# B2B_Connector.net
KiCad netlist of a schematic drawn in Altium Designer
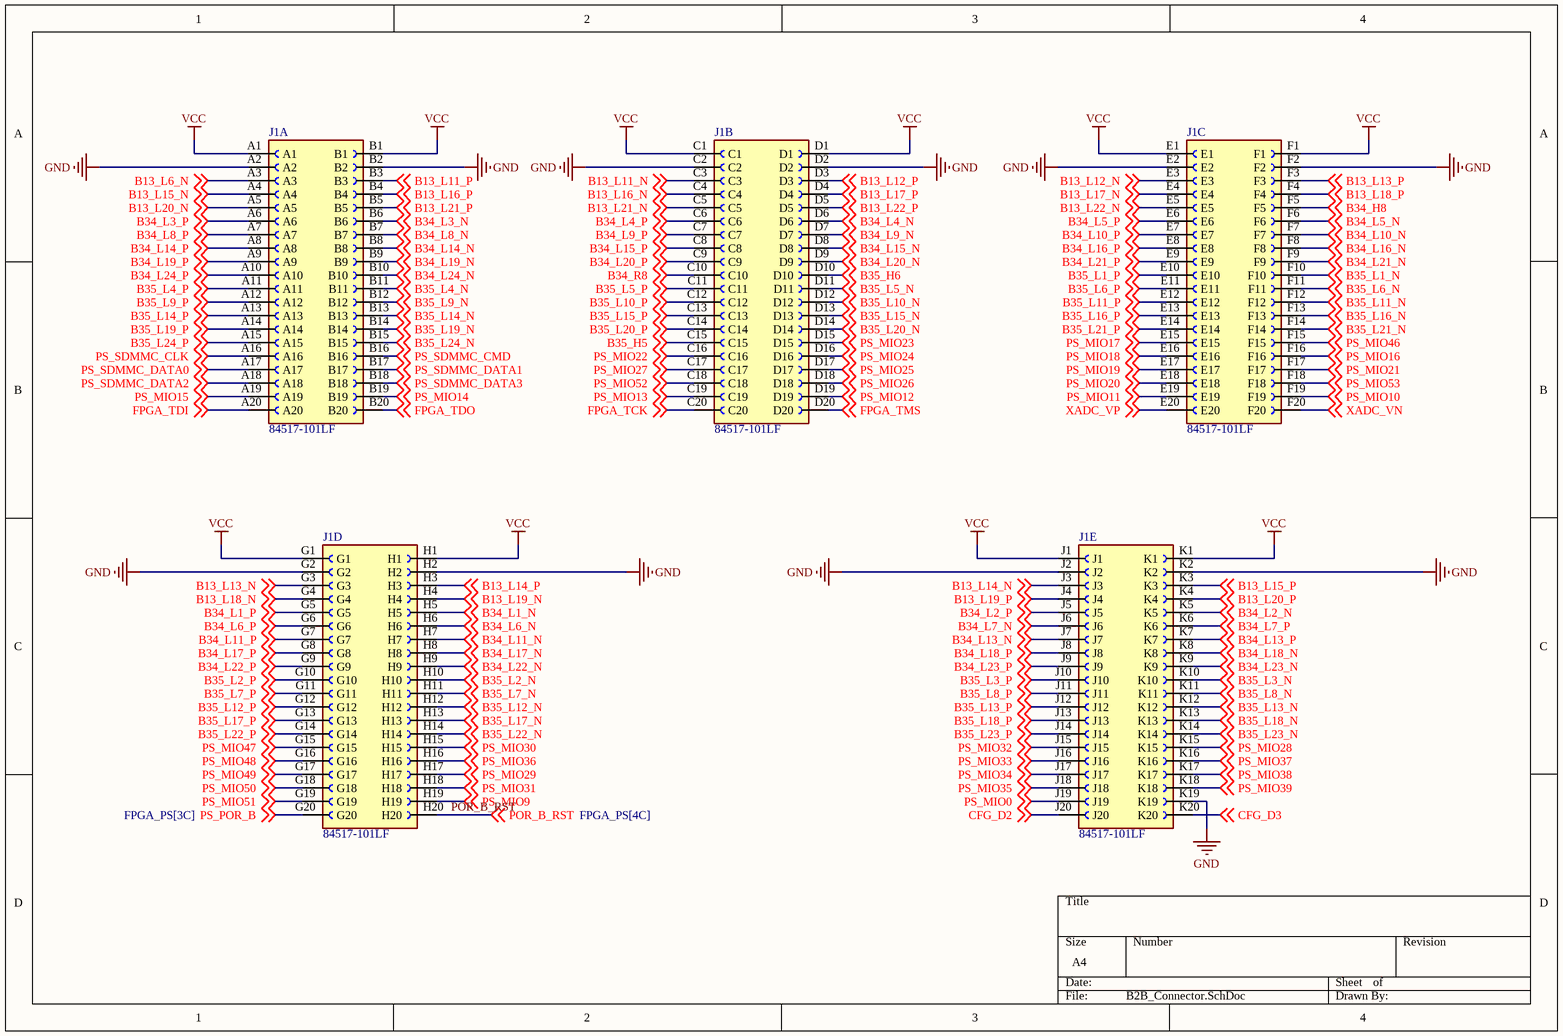
[diagram p0: B2B_Connector.SchDoc]

(export (version "E")
  (design (tool "Eeschema 10.0.6"))
  (components
    (comp (ref "J1")
      (value "84517-101LF")
      (footprint "AMPHENOL_84517-101LF")
      (description "MEG-ARRAY LEAD FREE-200 POS RECP 4MM W/CAP ¦ Amphenol FCI (Amphenol CS) 84517-101LF")
      (fields (field (name "MF") "Amphenol ICC (FCI)"))
      (libsource (lib "84517-101LF") (part "84517-101LF"))
    )
  )
  (nets
    (net (code "1") (name "B13_L6_N") (class "Default")
      (node (ref "J1") (pin "A3") (pinfunction "A3_A3") (pintype "passive"))
    )
    (net (code "2") (name "B13_L11_N") (class "Default")
      (node (ref "J1") (pin "C3") (pinfunction "C3_C3") (pintype "passive"))
    )
    (net (code "3") (name "B13_L11_P") (class "Default")
      (node (ref "J1") (pin "B3") (pinfunction "B3_B3") (pintype "passive"))
    )
    (net (code "4") (name "B13_L12_N") (class "Default")
      (node (ref "J1") (pin "E3") (pinfunction "E3_E3") (pintype "passive"))
    )
    (net (code "5") (name "B13_L12_P") (class "Default")
      (node (ref "J1") (pin "D3") (pinfunction "D3_D3") (pintype "passive"))
    )
    (net (code "6") (name "B13_L13_N") (class "Default")
      (node (ref "J1") (pin "G3") (pinfunction "G3_G3") (pintype "passive"))
    )
    (net (code "7") (name "B13_L13_P") (class "Default")
      (node (ref "J1") (pin "F3") (pinfunction "F3_F3") (pintype "passive"))
    )
    (net (code "8") (name "B13_L14_N") (class "Default")
      (node (ref "J1") (pin "J3") (pinfunction "J3_J3") (pintype "passive"))
    )
    (net (code "9") (name "B13_L14_P") (class "Default")
      (node (ref "J1") (pin "H3") (pinfunction "H3_H3") (pintype "passive"))
    )
    (net (code "10") (name "B13_L15_N") (class "Default")
      (node (ref "J1") (pin "A4") (pinfunction "A4_A4") (pintype "passive"))
    )
    (net (code "11") (name "B13_L15_P") (class "Default")
      (node (ref "J1") (pin "K3") (pinfunction "K3_K3") (pintype "passive"))
    )
    (net (code "12") (name "B13_L16_N") (class "Default")
      (node (ref "J1") (pin "C4") (pinfunction "C4_C4") (pintype "passive"))
    )
    (net (code "13") (name "B13_L16_P") (class "Default")
      (node (ref "J1") (pin "B4") (pinfunction "B4_B4") (pintype "passive"))
    )
    (net (code "14") (name "B13_L17_N") (class "Default")
      (node (ref "J1") (pin "E4") (pinfunction "E4_E4") (pintype "passive"))
    )
    (net (code "15") (name "B13_L17_P") (class "Default")
      (node (ref "J1") (pin "D4") (pinfunction "D4_D4") (pintype "passive"))
    )
    (net (code "16") (name "B13_L18_N") (class "Default")
      (node (ref "J1") (pin "G4") (pinfunction "G4_G4") (pintype "passive"))
    )
    (net (code "17") (name "B13_L18_P") (class "Default")
      (node (ref "J1") (pin "F4") (pinfunction "F4_F4") (pintype "passive"))
    )
    (net (code "18") (name "B13_L19_N") (class "Default")
      (node (ref "J1") (pin "H4") (pinfunction "H4_H4") (pintype "passive"))
    )
    (net (code "19") (name "B13_L19_P") (class "Default")
      (node (ref "J1") (pin "J4") (pinfunction "J4_J4") (pintype "passive"))
    )
    (net (code "20") (name "B13_L20_N") (class "Default")
      (node (ref "J1") (pin "A5") (pinfunction "A5_A5") (pintype "passive"))
    )
    (net (code "21") (name "B13_L20_P") (class "Default")
      (node (ref "J1") (pin "K4") (pinfunction "K4_K4") (pintype "passive"))
    )
    (net (code "22") (name "B13_L21_N") (class "Default")
      (node (ref "J1") (pin "C5") (pinfunction "C5_C5") (pintype "passive"))
    )
    (net (code "23") (name "B13_L21_P") (class "Default")
      (node (ref "J1") (pin "B5") (pinfunction "B5_B5") (pintype "passive"))
    )
    (net (code "24") (name "B13_L22_N") (class "Default")
      (node (ref "J1") (pin "E5") (pinfunction "E5_E5") (pintype "passive"))
    )
    (net (code "25") (name "B13_L22_P") (class "Default")
      (node (ref "J1") (pin "D5") (pinfunction "D5_D5") (pintype "passive"))
    )
    (net (code "26") (name "B34_H8") (class "Default")
      (node (ref "J1") (pin "F5") (pinfunction "F5_F5") (pintype "passive"))
    )
    (net (code "27") (name "B34_L1_N") (class "Default")
      (node (ref "J1") (pin "H5") (pinfunction "H5_H5") (pintype "passive"))
    )
    (net (code "28") (name "B34_L1_P") (class "Default")
      (node (ref "J1") (pin "G5") (pinfunction "G5_G5") (pintype "passive"))
    )
    (net (code "29") (name "B34_L2_N") (class "Default")
      (node (ref "J1") (pin "K5") (pinfunction "K5_K5") (pintype "passive"))
    )
    (net (code "30") (name "B34_L2_P") (class "Default")
      (node (ref "J1") (pin "J5") (pinfunction "J5_J5") (pintype "passive"))
    )
    (net (code "31") (name "B34_L3_N") (class "Default")
      (node (ref "J1") (pin "B6") (pinfunction "B6_B6") (pintype "passive"))
    )
    (net (code "32") (name "B34_L3_P") (class "Default")
      (node (ref "J1") (pin "A6") (pinfunction "A6_A6") (pintype "passive"))
    )
    (net (code "33") (name "B34_L4_N") (class "Default")
      (node (ref "J1") (pin "D6") (pinfunction "D6_D6") (pintype "passive"))
    )
    (net (code "34") (name "B34_L4_P") (class "Default")
      (node (ref "J1") (pin "C6") (pinfunction "C6_C6") (pintype "passive"))
    )
    (net (code "35") (name "B34_L5_N") (class "Default")
      (node (ref "J1") (pin "F6") (pinfunction "F6_F6") (pintype "passive"))
    )
    (net (code "36") (name "B34_L5_P") (class "Default")
      (node (ref "J1") (pin "E6") (pinfunction "E6_E6") (pintype "passive"))
    )
    (net (code "37") (name "B34_L6_N") (class "Default")
      (node (ref "J1") (pin "H6") (pinfunction "H6_H6") (pintype "passive"))
    )
    (net (code "38") (name "B34_L6_P") (class "Default")
      (node (ref "J1") (pin "G6") (pinfunction "G6_G6") (pintype "passive"))
    )
    (net (code "39") (name "B34_L7_N") (class "Default")
      (node (ref "J1") (pin "J6") (pinfunction "J6_J6") (pintype "passive"))
    )
    (net (code "40") (name "B34_L7_P") (class "Default")
      (node (ref "J1") (pin "K6") (pinfunction "K6_K6") (pintype "passive"))
    )
    (net (code "41") (name "B34_L8_N") (class "Default")
      (node (ref "J1") (pin "B7") (pinfunction "B7_B7") (pintype "passive"))
    )
    (net (code "42") (name "B34_L8_P") (class "Default")
      (node (ref "J1") (pin "A7") (pinfunction "A7_A7") (pintype "passive"))
    )
    (net (code "43") (name "B34_L9_N") (class "Default")
      (node (ref "J1") (pin "D7") (pinfunction "D7_D7") (pintype "passive"))
    )
    (net (code "44") (name "B34_L9_P") (class "Default")
      (node (ref "J1") (pin "C7") (pinfunction "C7_C7") (pintype "passive"))
    )
    (net (code "45") (name "B34_L10_N") (class "Default")
      (node (ref "J1") (pin "F7") (pinfunction "F7_F7") (pintype "passive"))
    )
    (net (code "46") (name "B34_L10_P") (class "Default")
      (node (ref "J1") (pin "E7") (pinfunction "E7_E7") (pintype "passive"))
    )
    (net (code "47") (name "B34_L11_N") (class "Default")
      (node (ref "J1") (pin "H7") (pinfunction "H7_H7") (pintype "passive"))
    )
    (net (code "48") (name "B34_L11_P") (class "Default")
      (node (ref "J1") (pin "G7") (pinfunction "G7_G7") (pintype "passive"))
    )
    (net (code "49") (name "B34_L13_N") (class "Default")
      (node (ref "J1") (pin "J7") (pinfunction "J7_J7") (pintype "passive"))
    )
    (net (code "50") (name "B34_L13_P") (class "Default")
      (node (ref "J1") (pin "K7") (pinfunction "K7_K7") (pintype "passive"))
    )
    (net (code "51") (name "B34_L14_N") (class "Default")
      (node (ref "J1") (pin "B8") (pinfunction "B8_B8") (pintype "passive"))
    )
    (net (code "52") (name "B34_L14_P") (class "Default")
      (node (ref "J1") (pin "A8") (pinfunction "A8_A8") (pintype "passive"))
    )
    (net (code "53") (name "B34_L15_N") (class "Default")
      (node (ref "J1") (pin "D8") (pinfunction "D8_D8") (pintype "passive"))
    )
    (net (code "54") (name "B34_L15_P") (class "Default")
      (node (ref "J1") (pin "C8") (pinfunction "C8_C8") (pintype "passive"))
    )
    (net (code "55") (name "B34_L16_N") (class "Default")
      (node (ref "J1") (pin "F8") (pinfunction "F8_F8") (pintype "passive"))
    )
    (net (code "56") (name "B34_L16_P") (class "Default")
      (node (ref "J1") (pin "E8") (pinfunction "E8_E8") (pintype "passive"))
    )
    (net (code "57") (name "B34_L17_N") (class "Default")
      (node (ref "J1") (pin "H8") (pinfunction "H8_H8") (pintype "passive"))
    )
    (net (code "58") (name "B34_L17_P") (class "Default")
      (node (ref "J1") (pin "G8") (pinfunction "G8_G8") (pintype "passive"))
    )
    (net (code "59") (name "B34_L18_N") (class "Default")
      (node (ref "J1") (pin "K8") (pinfunction "K8_K8") (pintype "passive"))
    )
    (net (code "60") (name "B34_L18_P") (class "Default")
      (node (ref "J1") (pin "J8") (pinfunction "J8_J8") (pintype "passive"))
    )
    (net (code "61") (name "B34_L19_N") (class "Default")
      (node (ref "J1") (pin "B9") (pinfunction "B9_B9") (pintype "passive"))
    )
    (net (code "62") (name "B34_L19_P") (class "Default")
      (node (ref "J1") (pin "A9") (pinfunction "A9_A9") (pintype "passive"))
    )
    (net (code "63") (name "B34_L20_N") (class "Default")
      (node (ref "J1") (pin "D9") (pinfunction "D9_D9") (pintype "passive"))
    )
    (net (code "64") (name "B34_L20_P") (class "Default")
      (node (ref "J1") (pin "C9") (pinfunction "C9_C9") (pintype "passive"))
    )
    (net (code "65") (name "B34_L21_N") (class "Default")
      (node (ref "J1") (pin "F9") (pinfunction "F9_F9") (pintype "passive"))
    )
    (net (code "66") (name "B34_L21_P") (class "Default")
      (node (ref "J1") (pin "E9") (pinfunction "E9_E9") (pintype "passive"))
    )
    (net (code "67") (name "B34_L22_N") (class "Default")
      (node (ref "J1") (pin "H9") (pinfunction "H9_H9") (pintype "passive"))
    )
    (net (code "68") (name "B34_L22_P") (class "Default")
      (node (ref "J1") (pin "G9") (pinfunction "G9_G9") (pintype "passive"))
    )
    (net (code "69") (name "B34_L23_N") (class "Default")
      (node (ref "J1") (pin "K9") (pinfunction "K9_K9") (pintype "passive"))
    )
    (net (code "70") (name "B34_L23_P") (class "Default")
      (node (ref "J1") (pin "J9") (pinfunction "J9_J9") (pintype "passive"))
    )
    (net (code "71") (name "B34_L24_N") (class "Default")
      (node (ref "J1") (pin "B10") (pinfunction "B10_B10") (pintype "passive"))
    )
    (net (code "72") (name "B34_L24_P") (class "Default")
      (node (ref "J1") (pin "A10") (pinfunction "A10_A10") (pintype "passive"))
    )
    (net (code "73") (name "B34_R8") (class "Default")
      (node (ref "J1") (pin "C10") (pinfunction "C10_C10") (pintype "passive"))
    )
    (net (code "74") (name "B35_H5") (class "Default")
      (node (ref "J1") (pin "C15") (pinfunction "C15_C15") (pintype "passive"))
    )
    (net (code "75") (name "B35_H6") (class "Default")
      (node (ref "J1") (pin "D10") (pinfunction "D10_D10") (pintype "passive"))
    )
    (net (code "76") (name "B35_L1_N") (class "Default")
      (node (ref "J1") (pin "F10") (pinfunction "F10_F10") (pintype "passive"))
    )
    (net (code "77") (name "B35_L1_P") (class "Default")
      (node (ref "J1") (pin "E10") (pinfunction "E10_E10") (pintype "passive"))
    )
    (net (code "78") (name "B35_L2_N") (class "Default")
      (node (ref "J1") (pin "H10") (pinfunction "H10_H10") (pintype "passive"))
    )
    (net (code "79") (name "B35_L2_P") (class "Default")
      (node (ref "J1") (pin "G10") (pinfunction "G10_G10") (pintype "passive"))
    )
    (net (code "80") (name "B35_L3_N") (class "Default")
      (node (ref "J1") (pin "K10") (pinfunction "K10_K10") (pintype "passive"))
    )
    (net (code "81") (name "B35_L3_P") (class "Default")
      (node (ref "J1") (pin "J10") (pinfunction "J10_J10") (pintype "passive"))
    )
    (net (code "82") (name "B35_L4_N") (class "Default")
      (node (ref "J1") (pin "B11") (pinfunction "B11_B11") (pintype "passive"))
    )
    (net (code "83") (name "B35_L4_P") (class "Default")
      (node (ref "J1") (pin "A11") (pinfunction "A11_A11") (pintype "passive"))
    )
    (net (code "84") (name "B35_L5_N") (class "Default")
      (node (ref "J1") (pin "D11") (pinfunction "D11_D11") (pintype "passive"))
    )
    (net (code "85") (name "B35_L5_P") (class "Default")
      (node (ref "J1") (pin "C11") (pinfunction "C11_C11") (pintype "passive"))
    )
    (net (code "86") (name "B35_L6_N") (class "Default")
      (node (ref "J1") (pin "F11") (pinfunction "F11_F11") (pintype "passive"))
    )
    (net (code "87") (name "B35_L6_P") (class "Default")
      (node (ref "J1") (pin "E11") (pinfunction "E11_E11") (pintype "passive"))
    )
    (net (code "88") (name "B35_L7_N") (class "Default")
      (node (ref "J1") (pin "H11") (pinfunction "H11_H11") (pintype "passive"))
    )
    (net (code "89") (name "B35_L7_P") (class "Default")
      (node (ref "J1") (pin "G11") (pinfunction "G11_G11") (pintype "passive"))
    )
    (net (code "90") (name "B35_L8_N") (class "Default")
      (node (ref "J1") (pin "K11") (pinfunction "K11_K11") (pintype "passive"))
    )
    (net (code "91") (name "B35_L8_P") (class "Default")
      (node (ref "J1") (pin "J11") (pinfunction "J11_J11") (pintype "passive"))
    )
    (net (code "92") (name "B35_L9_N") (class "Default")
      (node (ref "J1") (pin "B12") (pinfunction "B12_B12") (pintype "passive"))
    )
    (net (code "93") (name "B35_L9_P") (class "Default")
      (node (ref "J1") (pin "A12") (pinfunction "A12_A12") (pintype "passive"))
    )
    (net (code "94") (name "B35_L10_N") (class "Default")
      (node (ref "J1") (pin "D12") (pinfunction "D12_D12") (pintype "passive"))
    )
    (net (code "95") (name "B35_L10_P") (class "Default")
      (node (ref "J1") (pin "C12") (pinfunction "C12_C12") (pintype "passive"))
    )
    (net (code "96") (name "B35_L11_N") (class "Default")
      (node (ref "J1") (pin "F12") (pinfunction "F12_F12") (pintype "passive"))
    )
    (net (code "97") (name "B35_L11_P") (class "Default")
      (node (ref "J1") (pin "E12") (pinfunction "E12_E12") (pintype "passive"))
    )
    (net (code "98") (name "B35_L12_N") (class "Default")
      (node (ref "J1") (pin "H12") (pinfunction "H12_H12") (pintype "passive"))
    )
    (net (code "99") (name "B35_L12_P") (class "Default")
      (node (ref "J1") (pin "G12") (pinfunction "G12_G12") (pintype "passive"))
    )
    (net (code "100") (name "B35_L13_N") (class "Default")
      (node (ref "J1") (pin "K12") (pinfunction "K12_K12") (pintype "passive"))
    )
    (net (code "101") (name "B35_L13_P") (class "Default")
      (node (ref "J1") (pin "J12") (pinfunction "J12_J12") (pintype "passive"))
    )
    (net (code "102") (name "B35_L14_N") (class "Default")
      (node (ref "J1") (pin "B13") (pinfunction "B13_B13") (pintype "passive"))
    )
    (net (code "103") (name "B35_L14_P") (class "Default")
      (node (ref "J1") (pin "A13") (pinfunction "A13_A13") (pintype "passive"))
    )
    (net (code "104") (name "B35_L15_N") (class "Default")
      (node (ref "J1") (pin "D13") (pinfunction "D13_D13") (pintype "passive"))
    )
    (net (code "105") (name "B35_L15_P") (class "Default")
      (node (ref "J1") (pin "C13") (pinfunction "C13_C13") (pintype "passive"))
    )
    (net (code "106") (name "B35_L16_N") (class "Default")
      (node (ref "J1") (pin "F13") (pinfunction "F13_F13") (pintype "passive"))
    )
    (net (code "107") (name "B35_L16_P") (class "Default")
      (node (ref "J1") (pin "E13") (pinfunction "E13_E13") (pintype "passive"))
    )
    (net (code "108") (name "B35_L17_N") (class "Default")
      (node (ref "J1") (pin "H13") (pinfunction "H13_H13") (pintype "passive"))
    )
    (net (code "109") (name "B35_L17_P") (class "Default")
      (node (ref "J1") (pin "G13") (pinfunction "G13_G13") (pintype "passive"))
    )
    (net (code "110") (name "B35_L18_N") (class "Default")
      (node (ref "J1") (pin "K13") (pinfunction "K13_K13") (pintype "passive"))
    )
    (net (code "111") (name "B35_L18_P") (class "Default")
      (node (ref "J1") (pin "J13") (pinfunction "J13_J13") (pintype "passive"))
    )
    (net (code "112") (name "B35_L19_N") (class "Default")
      (node (ref "J1") (pin "B14") (pinfunction "B14_B14") (pintype "passive"))
    )
    (net (code "113") (name "B35_L19_P") (class "Default")
      (node (ref "J1") (pin "A14") (pinfunction "A14_A14") (pintype "passive"))
    )
    (net (code "114") (name "B35_L20_N") (class "Default")
      (node (ref "J1") (pin "D14") (pinfunction "D14_D14") (pintype "passive"))
    )
    (net (code "115") (name "B35_L20_P") (class "Default")
      (node (ref "J1") (pin "C14") (pinfunction "C14_C14") (pintype "passive"))
    )
    (net (code "116") (name "B35_L21_N") (class "Default")
      (node (ref "J1") (pin "F14") (pinfunction "F14_F14") (pintype "passive"))
    )
    (net (code "117") (name "B35_L21_P") (class "Default")
      (node (ref "J1") (pin "E14") (pinfunction "E14_E14") (pintype "passive"))
    )
    (net (code "118") (name "B35_L22_N") (class "Default")
      (node (ref "J1") (pin "H14") (pinfunction "H14_H14") (pintype "passive"))
    )
    (net (code "119") (name "B35_L22_P") (class "Default")
      (node (ref "J1") (pin "G14") (pinfunction "G14_G14") (pintype "passive"))
    )
    (net (code "120") (name "B35_L23_N") (class "Default")
      (node (ref "J1") (pin "K14") (pinfunction "K14_K14") (pintype "passive"))
    )
    (net (code "121") (name "B35_L23_P") (class "Default")
      (node (ref "J1") (pin "J14") (pinfunction "J14_J14") (pintype "passive"))
    )
    (net (code "122") (name "B35_L24_N") (class "Default")
      (node (ref "J1") (pin "B15") (pinfunction "B15_B15") (pintype "passive"))
    )
    (net (code "123") (name "B35_L24_P") (class "Default")
      (node (ref "J1") (pin "A15") (pinfunction "A15_A15") (pintype "passive"))
    )
    (net (code "124") (name "CFG_D2") (class "Default")
      (node (ref "J1") (pin "J20") (pinfunction "J20_J20") (pintype "passive"))
    )
    (net (code "125") (name "CFG_D3") (class "Default")
      (node (ref "J1") (pin "K20") (pinfunction "K20_K20") (pintype "passive"))
    )
    (net (code "126") (name "FPGA_TCK") (class "Default")
      (node (ref "J1") (pin "C20") (pinfunction "C20_C20") (pintype "passive"))
    )
    (net (code "127") (name "FPGA_TDI") (class "Default")
      (node (ref "J1") (pin "A20") (pinfunction "A20_A20") (pintype "passive"))
    )
    (net (code "128") (name "FPGA_TDO") (class "Default")
      (node (ref "J1") (pin "B20") (pinfunction "B20_B20") (pintype "passive"))
    )
    (net (code "129") (name "FPGA_TMS") (class "Default")
      (node (ref "J1") (pin "D20") (pinfunction "D20_D20") (pintype "passive"))
    )
    (net (code "130") (name "GND") (class "Default")
      (node (ref "J1") (pin "A2") (pinfunction "A2_A2") (pintype "passive"))
      (node (ref "J1") (pin "B2") (pinfunction "B2_B2") (pintype "passive"))
      (node (ref "J1") (pin "C2") (pinfunction "C2_C2") (pintype "passive"))
      (node (ref "J1") (pin "D2") (pinfunction "D2_D2") (pintype "passive"))
      (node (ref "J1") (pin "E2") (pinfunction "E2_E2") (pintype "passive"))
      (node (ref "J1") (pin "F2") (pinfunction "F2_F2") (pintype "passive"))
      (node (ref "J1") (pin "G2") (pinfunction "G2_G2") (pintype "passive"))
      (node (ref "J1") (pin "H2") (pinfunction "H2_H2") (pintype "passive"))
      (node (ref "J1") (pin "J2") (pinfunction "J2_J2") (pintype "passive"))
      (node (ref "J1") (pin "K19") (pinfunction "K19_K19") (pintype "passive"))
      (node (ref "J1") (pin "K2") (pinfunction "K2_K2") (pintype "passive"))
    )
    (net (code "131") (name "POR_B_RST") (class "Default")
      (node (ref "J1") (pin "H20") (pinfunction "H20_H20") (pintype "passive"))
    )
    (net (code "132") (name "PS_MIO0") (class "Default")
      (node (ref "J1") (pin "J19") (pinfunction "J19_J19") (pintype "passive"))
    )
    (net (code "133") (name "PS_MIO9") (class "Default")
      (node (ref "J1") (pin "H19") (pinfunction "H19_H19") (pintype "passive"))
    )
    (net (code "134") (name "PS_MIO10") (class "Default")
      (node (ref "J1") (pin "F19") (pinfunction "F19_F19") (pintype "passive"))
    )
    (net (code "135") (name "PS_MIO11") (class "Default")
      (node (ref "J1") (pin "E19") (pinfunction "E19_E19") (pintype "passive"))
    )
    (net (code "136") (name "PS_MIO12") (class "Default")
      (node (ref "J1") (pin "D19") (pinfunction "D19_D19") (pintype "passive"))
    )
    (net (code "137") (name "PS_MIO13") (class "Default")
      (node (ref "J1") (pin "C19") (pinfunction "C19_C19") (pintype "passive"))
    )
    (net (code "138") (name "PS_MIO14") (class "Default")
      (node (ref "J1") (pin "B19") (pinfunction "B19_B19") (pintype "passive"))
    )
    (net (code "139") (name "PS_MIO15") (class "Default")
      (node (ref "J1") (pin "A19") (pinfunction "A19_A19") (pintype "passive"))
    )
    (net (code "140") (name "PS_MIO16") (class "Default")
      (node (ref "J1") (pin "F16") (pinfunction "F16_F16") (pintype "passive"))
    )
    (net (code "141") (name "PS_MIO17") (class "Default")
      (node (ref "J1") (pin "E15") (pinfunction "E15_E15") (pintype "passive"))
    )
    (net (code "142") (name "PS_MIO18") (class "Default")
      (node (ref "J1") (pin "E16") (pinfunction "E16_E16") (pintype "passive"))
    )
    (net (code "143") (name "PS_MIO19") (class "Default")
      (node (ref "J1") (pin "E17") (pinfunction "E17_E17") (pintype "passive"))
    )
    (net (code "144") (name "PS_MIO20") (class "Default")
      (node (ref "J1") (pin "E18") (pinfunction "E18_E18") (pintype "passive"))
    )
    (net (code "145") (name "PS_MIO21") (class "Default")
      (node (ref "J1") (pin "F17") (pinfunction "F17_F17") (pintype "passive"))
    )
    (net (code "146") (name "PS_MIO22") (class "Default")
      (node (ref "J1") (pin "C16") (pinfunction "C16_C16") (pintype "passive"))
    )
    (net (code "147") (name "PS_MIO23") (class "Default")
      (node (ref "J1") (pin "D15") (pinfunction "D15_D15") (pintype "passive"))
    )
    (net (code "148") (name "PS_MIO24") (class "Default")
      (node (ref "J1") (pin "D16") (pinfunction "D16_D16") (pintype "passive"))
    )
    (net (code "149") (name "PS_MIO25") (class "Default")
      (node (ref "J1") (pin "D17") (pinfunction "D17_D17") (pintype "passive"))
    )
    (net (code "150") (name "PS_MIO26") (class "Default")
      (node (ref "J1") (pin "D18") (pinfunction "D18_D18") (pintype "passive"))
    )
    (net (code "151") (name "PS_MIO27") (class "Default")
      (node (ref "J1") (pin "C17") (pinfunction "C17_C17") (pintype "passive"))
    )
    (net (code "152") (name "PS_MIO28") (class "Default")
      (node (ref "J1") (pin "K15") (pinfunction "K15_K15") (pintype "passive"))
    )
    (net (code "153") (name "PS_MIO29") (class "Default")
      (node (ref "J1") (pin "H17") (pinfunction "H17_H17") (pintype "passive"))
    )
    (net (code "154") (name "PS_MIO30") (class "Default")
      (node (ref "J1") (pin "H15") (pinfunction "H15_H15") (pintype "passive"))
    )
    (net (code "155") (name "PS_MIO31") (class "Default")
      (node (ref "J1") (pin "H18") (pinfunction "H18_H18") (pintype "passive"))
    )
    (net (code "156") (name "PS_MIO32") (class "Default")
      (node (ref "J1") (pin "J15") (pinfunction "J15_J15") (pintype "passive"))
    )
    (net (code "157") (name "PS_MIO33") (class "Default")
      (node (ref "J1") (pin "J16") (pinfunction "J16_J16") (pintype "passive"))
    )
    (net (code "158") (name "PS_MIO34") (class "Default")
      (node (ref "J1") (pin "J17") (pinfunction "J17_J17") (pintype "passive"))
    )
    (net (code "159") (name "PS_MIO35") (class "Default")
      (node (ref "J1") (pin "J18") (pinfunction "J18_J18") (pintype "passive"))
    )
    (net (code "160") (name "PS_MIO36") (class "Default")
      (node (ref "J1") (pin "H16") (pinfunction "H16_H16") (pintype "passive"))
    )
    (net (code "161") (name "PS_MIO37") (class "Default")
      (node (ref "J1") (pin "K16") (pinfunction "K16_K16") (pintype "passive"))
    )
    (net (code "162") (name "PS_MIO38") (class "Default")
      (node (ref "J1") (pin "K17") (pinfunction "K17_K17") (pintype "passive"))
    )
    (net (code "163") (name "PS_MIO39") (class "Default")
      (node (ref "J1") (pin "K18") (pinfunction "K18_K18") (pintype "passive"))
    )
    (net (code "164") (name "PS_MIO46") (class "Default")
      (node (ref "J1") (pin "F15") (pinfunction "F15_F15") (pintype "passive"))
    )
    (net (code "165") (name "PS_MIO47") (class "Default")
      (node (ref "J1") (pin "G15") (pinfunction "G15_G15") (pintype "passive"))
    )
    (net (code "166") (name "PS_MIO48") (class "Default")
      (node (ref "J1") (pin "G16") (pinfunction "G16_G16") (pintype "passive"))
    )
    (net (code "167") (name "PS_MIO49") (class "Default")
      (node (ref "J1") (pin "G17") (pinfunction "G17_G17") (pintype "passive"))
    )
    (net (code "168") (name "PS_MIO50") (class "Default")
      (node (ref "J1") (pin "G18") (pinfunction "G18_G18") (pintype "passive"))
    )
    (net (code "169") (name "PS_MIO51") (class "Default")
      (node (ref "J1") (pin "G19") (pinfunction "G19_G19") (pintype "passive"))
    )
    (net (code "170") (name "PS_MIO52") (class "Default")
      (node (ref "J1") (pin "C18") (pinfunction "C18_C18") (pintype "passive"))
    )
    (net (code "171") (name "PS_MIO53") (class "Default")
      (node (ref "J1") (pin "F18") (pinfunction "F18_F18") (pintype "passive"))
    )
    (net (code "172") (name "PS_POR_B") (class "Default")
      (node (ref "J1") (pin "G20") (pinfunction "G20_G20") (pintype "passive"))
    )
    (net (code "173") (name "PS_SDMMC_CLK") (class "Default")
      (node (ref "J1") (pin "A16") (pinfunction "A16_A16") (pintype "passive"))
    )
    (net (code "174") (name "PS_SDMMC_CMD") (class "Default")
      (node (ref "J1") (pin "B16") (pinfunction "B16_B16") (pintype "passive"))
    )
    (net (code "175") (name "PS_SDMMC_DATA0") (class "Default")
      (node (ref "J1") (pin "A17") (pinfunction "A17_A17") (pintype "passive"))
    )
    (net (code "176") (name "PS_SDMMC_DATA1") (class "Default")
      (node (ref "J1") (pin "B17") (pinfunction "B17_B17") (pintype "passive"))
    )
    (net (code "177") (name "PS_SDMMC_DATA2") (class "Default")
      (node (ref "J1") (pin "A18") (pinfunction "A18_A18") (pintype "passive"))
    )
    (net (code "178") (name "PS_SDMMC_DATA3") (class "Default")
      (node (ref "J1") (pin "B18") (pinfunction "B18_B18") (pintype "passive"))
    )
    (net (code "179") (name "VCC") (class "Default")
      (node (ref "J1") (pin "A1") (pinfunction "A1_A1") (pintype "passive"))
      (node (ref "J1") (pin "B1") (pinfunction "B1_B1") (pintype "passive"))
      (node (ref "J1") (pin "C1") (pinfunction "C1_C1") (pintype "passive"))
      (node (ref "J1") (pin "D1") (pinfunction "D1_D1") (pintype "passive"))
      (node (ref "J1") (pin "E1") (pinfunction "E1_E1") (pintype "passive"))
      (node (ref "J1") (pin "F1") (pinfunction "F1_F1") (pintype "passive"))
      (node (ref "J1") (pin "G1") (pinfunction "G1_G1") (pintype "passive"))
      (node (ref "J1") (pin "H1") (pinfunction "H1_H1") (pintype "passive"))
      (node (ref "J1") (pin "J1") (pinfunction "J1_J1") (pintype "passive"))
      (node (ref "J1") (pin "K1") (pinfunction "K1_K1") (pintype "passive"))
    )
    (net (code "180") (name "XADC_VN") (class "Default")
      (node (ref "J1") (pin "F20") (pinfunction "F20_F20") (pintype "passive"))
    )
    (net (code "181") (name "XADC_VP") (class "Default")
      (node (ref "J1") (pin "E20") (pinfunction "E20_E20") (pintype "passive"))
    )
  )
)
